# power.net
KiCad netlist of a schematic drawn in Altium Designer
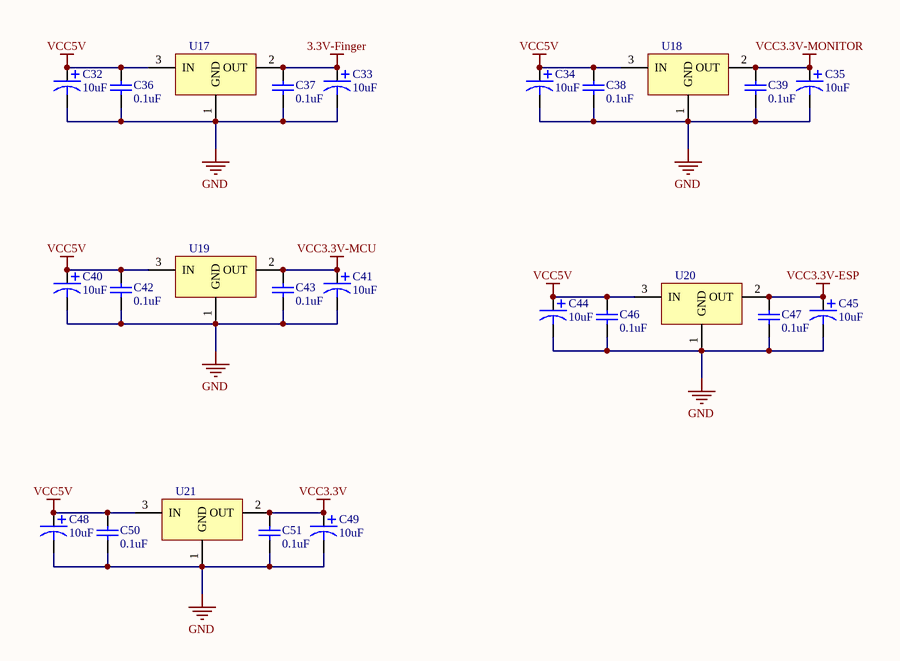
[diagram p0: power.SchDoc]

(export (version "E")
  (design (tool "Eeschema 10.0.6"))
  (components
    (comp (ref "C32")
      (value "10uF")
      (footprint "1206_C")
      (description "贴片电容，1206")
      (libsource (lib "MES-terminal") (part "CAPACITOR"))
    )
    (comp (ref "C33")
      (value "10uF")
      (footprint "1206_C")
      (description "贴片电容，1206")
      (libsource (lib "MES-terminal") (part "CAPACITOR"))
    )
    (comp (ref "C34")
      (value "10uF")
      (footprint "1206_C")
      (description "贴片电容，1206")
      (libsource (lib "MES-terminal") (part "CAPACITOR"))
    )
    (comp (ref "C35")
      (value "10uF")
      (footprint "1206_C")
      (description "贴片电容，1206")
      (libsource (lib "MES-terminal") (part "CAPACITOR"))
    )
    (comp (ref "C36")
      (value "0.1uF")
      (footprint "0603_C")
      (description "贴片电容，0603")
      (libsource (lib "stm8l052r8t6开发板") (part "Cap"))
    )
    (comp (ref "C37")
      (value "0.1uF")
      (footprint "0603_C")
      (description "贴片电容，0603")
      (libsource (lib "stm8l052r8t6开发板") (part "Cap"))
    )
    (comp (ref "C38")
      (value "0.1uF")
      (footprint "0603_C")
      (description "贴片电容，0603")
      (libsource (lib "stm8l052r8t6开发板") (part "Cap"))
    )
    (comp (ref "C39")
      (value "0.1uF")
      (footprint "0603_C")
      (description "贴片电容，0603")
      (libsource (lib "stm8l052r8t6开发板") (part "Cap"))
    )
    (comp (ref "C40")
      (value "10uF")
      (footprint "1206_C")
      (description "贴片电容，1206")
      (libsource (lib "MES-terminal") (part "CAPACITOR"))
    )
    (comp (ref "C41")
      (value "10uF")
      (footprint "1206_C")
      (description "贴片电容，1206")
      (libsource (lib "MES-terminal") (part "CAPACITOR"))
    )
    (comp (ref "C42")
      (value "0.1uF")
      (footprint "0603_C")
      (description "贴片电容，0603")
      (libsource (lib "stm8l052r8t6开发板") (part "Cap"))
    )
    (comp (ref "C43")
      (value "0.1uF")
      (footprint "0603_C")
      (description "贴片电容，0603")
      (libsource (lib "stm8l052r8t6开发板") (part "Cap"))
    )
    (comp (ref "C44")
      (value "10uF")
      (footprint "1206_C")
      (description "贴片电容，1206")
      (libsource (lib "MES-terminal") (part "CAPACITOR"))
    )
    (comp (ref "C45")
      (value "10uF")
      (footprint "1206_C")
      (description "贴片电容，1206")
      (libsource (lib "MES-terminal") (part "CAPACITOR"))
    )
    (comp (ref "C46")
      (value "0.1uF")
      (footprint "0603_C")
      (description "贴片电容，0603")
      (libsource (lib "stm8l052r8t6开发板") (part "Cap"))
    )
    (comp (ref "C47")
      (value "0.1uF")
      (footprint "0603_C")
      (description "贴片电容，0603")
      (libsource (lib "stm8l052r8t6开发板") (part "Cap"))
    )
    (comp (ref "C48")
      (value "10uF")
      (footprint "1206_C")
      (description "贴片电容，1206")
      (libsource (lib "MES-terminal") (part "CAPACITOR"))
    )
    (comp (ref "C49")
      (value "10uF")
      (footprint "1206_C")
      (description "贴片电容，1206")
      (libsource (lib "MES-terminal") (part "CAPACITOR"))
    )
    (comp (ref "C50")
      (value "0.1uF")
      (footprint "0603_C")
      (description "贴片电容，0603")
      (libsource (lib "stm8l052r8t6开发板") (part "Cap"))
    )
    (comp (ref "C51")
      (value "0.1uF")
      (footprint "0603_C")
      (description "贴片电容，0603")
      (libsource (lib "stm8l052r8t6开发板") (part "Cap"))
    )
    (comp (ref "U17")
      (value "LM1117")
      (footprint "SOT-223")
      (libsource (lib "stm8l052r8t6开发板") (part "LM1117"))
    )
    (comp (ref "U18")
      (value "LM1117")
      (footprint "SOT-223")
      (libsource (lib "stm8l052r8t6开发板") (part "LM1117"))
    )
    (comp (ref "U19")
      (value "LM1117")
      (footprint "SOT-223")
      (libsource (lib "stm8l052r8t6开发板") (part "LM1117"))
    )
    (comp (ref "U20")
      (value "LM1117")
      (footprint "SOT-223")
      (libsource (lib "stm8l052r8t6开发板") (part "LM1117"))
    )
    (comp (ref "U21")
      (value "LM1117")
      (footprint "SOT-223")
      (libsource (lib "stm8l052r8t6开发板") (part "LM1117"))
    )
  )
  (nets
    (net (code "1") (name "3.3V-Finger") (class "Default")
      (node (ref "C33") (pin "1") (pinfunction "1_1") (pintype "passive"))
      (node (ref "C37") (pin "1") (pinfunction "1_1") (pintype "passive"))
      (node (ref "U17") (pin "2") (pinfunction "OUT_2") (pintype "passive"))
    )
    (net (code "2") (name "GND") (class "Default")
      (node (ref "C32") (pin "2") (pinfunction "2_2") (pintype "passive"))
      (node (ref "C33") (pin "2") (pinfunction "2_2") (pintype "passive"))
      (node (ref "C34") (pin "2") (pinfunction "2_2") (pintype "passive"))
      (node (ref "C35") (pin "2") (pinfunction "2_2") (pintype "passive"))
      (node (ref "C36") (pin "2") (pinfunction "2_2") (pintype "passive"))
      (node (ref "C37") (pin "2") (pinfunction "2_2") (pintype "passive"))
      (node (ref "C38") (pin "2") (pinfunction "2_2") (pintype "passive"))
      (node (ref "C39") (pin "2") (pinfunction "2_2") (pintype "passive"))
      (node (ref "C40") (pin "2") (pinfunction "2_2") (pintype "passive"))
      (node (ref "C41") (pin "2") (pinfunction "2_2") (pintype "passive"))
      (node (ref "C42") (pin "2") (pinfunction "2_2") (pintype "passive"))
      (node (ref "C43") (pin "2") (pinfunction "2_2") (pintype "passive"))
      (node (ref "C44") (pin "2") (pinfunction "2_2") (pintype "passive"))
      (node (ref "C45") (pin "2") (pinfunction "2_2") (pintype "passive"))
      (node (ref "C46") (pin "2") (pinfunction "2_2") (pintype "passive"))
      (node (ref "C47") (pin "2") (pinfunction "2_2") (pintype "passive"))
      (node (ref "C48") (pin "2") (pinfunction "2_2") (pintype "passive"))
      (node (ref "C49") (pin "2") (pinfunction "2_2") (pintype "passive"))
      (node (ref "C50") (pin "2") (pinfunction "2_2") (pintype "passive"))
      (node (ref "C51") (pin "2") (pinfunction "2_2") (pintype "passive"))
      (node (ref "U17") (pin "1") (pinfunction "GND_1") (pintype "passive"))
      (node (ref "U18") (pin "1") (pinfunction "GND_1") (pintype "passive"))
      (node (ref "U19") (pin "1") (pinfunction "GND_1") (pintype "passive"))
      (node (ref "U20") (pin "1") (pinfunction "GND_1") (pintype "passive"))
      (node (ref "U21") (pin "1") (pinfunction "GND_1") (pintype "passive"))
    )
    (net (code "3") (name "VCC3.3V") (class "Default")
      (node (ref "C49") (pin "1") (pinfunction "1_1") (pintype "passive"))
      (node (ref "C51") (pin "1") (pinfunction "1_1") (pintype "passive"))
      (node (ref "U21") (pin "2") (pinfunction "OUT_2") (pintype "passive"))
    )
    (net (code "4") (name "VCC3.3V-ESP") (class "Default")
      (node (ref "C45") (pin "1") (pinfunction "1_1") (pintype "passive"))
      (node (ref "C47") (pin "1") (pinfunction "1_1") (pintype "passive"))
      (node (ref "U20") (pin "2") (pinfunction "OUT_2") (pintype "passive"))
    )
    (net (code "5") (name "VCC3.3V-MCU") (class "Default")
      (node (ref "C41") (pin "1") (pinfunction "1_1") (pintype "passive"))
      (node (ref "C43") (pin "1") (pinfunction "1_1") (pintype "passive"))
      (node (ref "U19") (pin "2") (pinfunction "OUT_2") (pintype "passive"))
    )
    (net (code "6") (name "VCC3.3V-MONITOR") (class "Default")
      (node (ref "C35") (pin "1") (pinfunction "1_1") (pintype "passive"))
      (node (ref "C39") (pin "1") (pinfunction "1_1") (pintype "passive"))
      (node (ref "U18") (pin "2") (pinfunction "OUT_2") (pintype "passive"))
    )
    (net (code "7") (name "VCC5V") (class "Default")
      (node (ref "C32") (pin "1") (pinfunction "1_1") (pintype "passive"))
      (node (ref "C34") (pin "1") (pinfunction "1_1") (pintype "passive"))
      (node (ref "C36") (pin "1") (pinfunction "1_1") (pintype "passive"))
      (node (ref "C38") (pin "1") (pinfunction "1_1") (pintype "passive"))
      (node (ref "C40") (pin "1") (pinfunction "1_1") (pintype "passive"))
      (node (ref "C42") (pin "1") (pinfunction "1_1") (pintype "passive"))
      (node (ref "C44") (pin "1") (pinfunction "1_1") (pintype "passive"))
      (node (ref "C46") (pin "1") (pinfunction "1_1") (pintype "passive"))
      (node (ref "C48") (pin "1") (pinfunction "1_1") (pintype "passive"))
      (node (ref "C50") (pin "1") (pinfunction "1_1") (pintype "passive"))
      (node (ref "U17") (pin "3") (pinfunction "IN_3") (pintype "passive"))
      (node (ref "U18") (pin "3") (pinfunction "IN_3") (pintype "passive"))
      (node (ref "U19") (pin "3") (pinfunction "IN_3") (pintype "passive"))
      (node (ref "U20") (pin "3") (pinfunction "IN_3") (pintype "passive"))
      (node (ref "U21") (pin "3") (pinfunction "IN_3") (pintype "passive"))
    )
  )
)
